# centerpoint.net
KiCad netlist of a schematic drawn in EAGLE
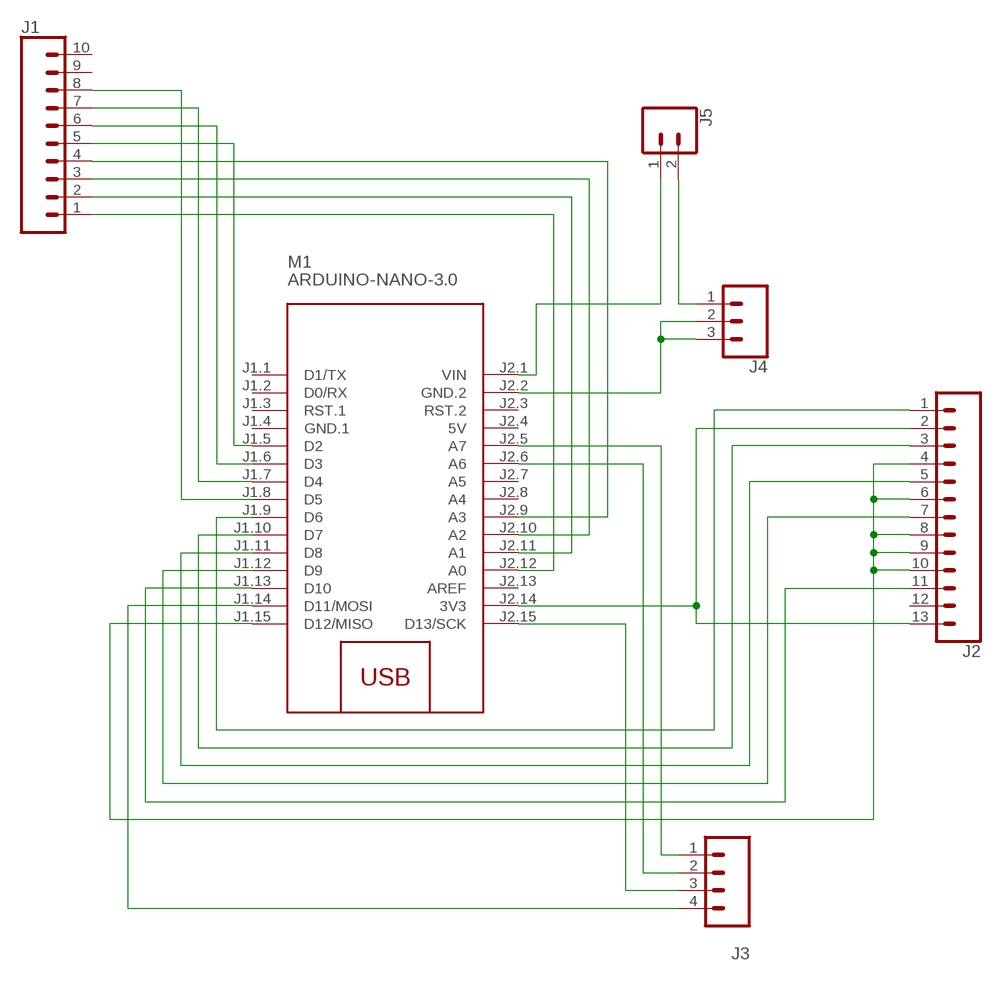
[diagram p0: schematic, sheet 1]

(export (version "E")
  (design (tool "Eeschema 10.0.6"))
  (components
    (comp (ref "J1")
      (value "CONN_10\"")
      (footprint "eagle-import:1X10")
      (libsource (lib "eagle-import") (part "CONN_10{dblquote}"))
    )
    (comp (ref "J2")
      (value "CONN_13")
      (footprint "eagle-import:1X13")
      (libsource (lib "eagle-import") (part "CONN_13"))
    )
    (comp (ref "J3")
      (value "CONN_04PTH")
      (footprint "eagle-import:1X04")
      (libsource (lib "eagle-import") (part "CONN_04PTH"))
    )
    (comp (ref "J4")
      (value "CONN_03-SCREW-5MM")
      (footprint "eagle-import:SCREWTERMINAL-5MM-3")
      (libsource (lib "eagle-import") (part "CONN_03-SCREW-5MM"))
    )
    (comp (ref "J5")
      (value "CONN_023.5MM")
      (footprint "eagle-import:SCREWTERMINAL-3.5MM-2")
      (libsource (lib "eagle-import") (part "CONN_023.5MM"))
    )
    (comp (ref "M1")
      (value "ARDUINO-NANO-3.0")
      (footprint "eagle-import:ARDUINO-NANO-3.0")
      (libsource (lib "eagle-import") (part "ARDUINO-NANO-3.0"))
    )
  )
  (nets
    (net (code "1") (name "/5V") (class "Default")
      (node (ref "M1") (pin "J2.4") (pinfunction "5V_J2.4") (pintype "power_in"))
    )
    (net (code "2") (name "/GND.1") (class "Default")
      (node (ref "M1") (pin "J1.4") (pinfunction "GND.1_J1.4") (pintype "power_in"))
    )
    (net (code "3") (name "Net-(J4-Pad1)") (class "Default")
      (node (ref "J4") (pin "1") (pinfunction "1_1") (pintype "passive"))
      (node (ref "J5") (pin "2") (pinfunction "2_2") (pintype "passive"))
    )
    (net (code "4") (name "Net-(M1-3V3)") (class "Default")
      (node (ref "J2") (pin "13") (pinfunction "13_13") (pintype "passive"))
      (node (ref "J2") (pin "2") (pinfunction "2_2") (pintype "passive"))
      (node (ref "M1") (pin "J2.14") (pinfunction "3V3_J2.14") (pintype "power_in"))
    )
    (net (code "5") (name "Net-(M1-A0)") (class "Default")
      (node (ref "J1") (pin "1") (pinfunction "1_1") (pintype "passive"))
      (node (ref "M1") (pin "J2.12") (pinfunction "A0_J2.12") (pintype "bidirectional"))
    )
    (net (code "6") (name "Net-(M1-A1)") (class "Default")
      (node (ref "J1") (pin "2") (pinfunction "2_2") (pintype "passive"))
      (node (ref "M1") (pin "J2.11") (pinfunction "A1_J2.11") (pintype "bidirectional"))
    )
    (net (code "7") (name "Net-(M1-A2)") (class "Default")
      (node (ref "J1") (pin "3") (pinfunction "3_3") (pintype "passive"))
      (node (ref "M1") (pin "J2.10") (pinfunction "A2_J2.10") (pintype "bidirectional"))
    )
    (net (code "8") (name "Net-(M1-A3)") (class "Default")
      (node (ref "J1") (pin "4") (pinfunction "4_4") (pintype "passive"))
      (node (ref "M1") (pin "J2.9") (pinfunction "A3_J2.9") (pintype "bidirectional"))
    )
    (net (code "9") (name "Net-(M1-A6)") (class "Default")
      (node (ref "J3") (pin "2") (pinfunction "2_2") (pintype "passive"))
      (node (ref "M1") (pin "J2.6") (pinfunction "A6_J2.6") (pintype "bidirectional"))
    )
    (net (code "10") (name "Net-(M1-A7)") (class "Default")
      (node (ref "J3") (pin "1") (pinfunction "1_1") (pintype "passive"))
      (node (ref "M1") (pin "J2.5") (pinfunction "A7_J2.5") (pintype "bidirectional"))
    )
    (net (code "11") (name "Net-(M1-D2)") (class "Default")
      (node (ref "J1") (pin "5") (pinfunction "5_5") (pintype "passive"))
      (node (ref "M1") (pin "J1.5") (pinfunction "D2_J1.5") (pintype "bidirectional"))
    )
    (net (code "12") (name "Net-(M1-D3)") (class "Default")
      (node (ref "J1") (pin "6") (pinfunction "6_6") (pintype "passive"))
      (node (ref "M1") (pin "J1.6") (pinfunction "D3_J1.6") (pintype "bidirectional"))
    )
    (net (code "13") (name "Net-(M1-D4)") (class "Default")
      (node (ref "J1") (pin "7") (pinfunction "7_7") (pintype "passive"))
      (node (ref "M1") (pin "J1.7") (pinfunction "D4_J1.7") (pintype "bidirectional"))
    )
    (net (code "14") (name "Net-(M1-D5)") (class "Default")
      (node (ref "J1") (pin "8") (pinfunction "8_8") (pintype "passive"))
      (node (ref "M1") (pin "J1.8") (pinfunction "D5_J1.8") (pintype "bidirectional"))
    )
    (net (code "15") (name "Net-(M1-D6)") (class "Default")
      (node (ref "J2") (pin "1") (pinfunction "1_1") (pintype "passive"))
      (node (ref "M1") (pin "J1.9") (pinfunction "D6_J1.9") (pintype "bidirectional"))
    )
    (net (code "16") (name "Net-(M1-D7)") (class "Default")
      (node (ref "J2") (pin "3") (pinfunction "3_3") (pintype "passive"))
      (node (ref "M1") (pin "J1.10") (pinfunction "D7_J1.10") (pintype "bidirectional"))
    )
    (net (code "17") (name "Net-(M1-D8)") (class "Default")
      (node (ref "J2") (pin "5") (pinfunction "5_5") (pintype "passive"))
      (node (ref "M1") (pin "J1.11") (pinfunction "D8_J1.11") (pintype "bidirectional"))
    )
    (net (code "18") (name "Net-(M1-D9)") (class "Default")
      (node (ref "J2") (pin "7") (pinfunction "7_7") (pintype "passive"))
      (node (ref "M1") (pin "J1.12") (pinfunction "D9_J1.12") (pintype "bidirectional"))
    )
    (net (code "19") (name "Net-(M1-D10)") (class "Default")
      (node (ref "J2") (pin "11") (pinfunction "11_11") (pintype "passive"))
      (node (ref "M1") (pin "J1.13") (pinfunction "D10_J1.13") (pintype "bidirectional"))
    )
    (net (code "20") (name "Net-(M1-D11{slash}MOSI)") (class "Default")
      (node (ref "J3") (pin "4") (pinfunction "4_4") (pintype "passive"))
      (node (ref "M1") (pin "J1.14") (pinfunction "D11/MOSI_J1.14") (pintype "bidirectional"))
    )
    (net (code "21") (name "Net-(M1-D12{slash}MISO)") (class "Default")
      (node (ref "J2") (pin "10") (pinfunction "10_10") (pintype "passive"))
      (node (ref "J2") (pin "4") (pinfunction "4_4") (pintype "passive"))
      (node (ref "J2") (pin "6") (pinfunction "6_6") (pintype "passive"))
      (node (ref "J2") (pin "8") (pinfunction "8_8") (pintype "passive"))
      (node (ref "J2") (pin "9") (pinfunction "9_9") (pintype "passive"))
      (node (ref "M1") (pin "J1.15") (pinfunction "D12/MISO_J1.15") (pintype "bidirectional"))
    )
    (net (code "22") (name "Net-(M1-D13{slash}SCK)") (class "Default")
      (node (ref "J3") (pin "3") (pinfunction "3_3") (pintype "passive"))
      (node (ref "M1") (pin "J2.15") (pinfunction "D13/SCK_J2.15") (pintype "bidirectional"))
    )
    (net (code "23") (name "Net-(M1-GND.2)") (class "Default")
      (node (ref "J4") (pin "2") (pinfunction "2_2") (pintype "passive"))
      (node (ref "J4") (pin "3") (pinfunction "3_3") (pintype "passive"))
      (node (ref "M1") (pin "J2.2") (pinfunction "GND.2_J2.2") (pintype "power_in"))
    )
    (net (code "24") (name "Net-(M1-VIN)") (class "Default")
      (node (ref "J5") (pin "1") (pinfunction "1_1") (pintype "passive"))
      (node (ref "M1") (pin "J2.1") (pinfunction "VIN_J2.1") (pintype "power_in"))
    )
    (net (code "25") (name "unconnected-(J1-Pad9)") (class "Default")
      (node (ref "J1") (pin "9") (pinfunction "9_9") (pintype "passive"))
    )
    (net (code "26") (name "unconnected-(J1-Pad10)") (class "Default")
      (node (ref "J1") (pin "10") (pinfunction "10_10") (pintype "passive"))
    )
    (net (code "27") (name "unconnected-(J2-Pad12)") (class "Default")
      (node (ref "J2") (pin "12") (pinfunction "12_12") (pintype "passive"))
    )
    (net (code "28") (name "unconnected-(M1-A4-PadJ2.8)") (class "Default")
      (node (ref "M1") (pin "J2.8") (pinfunction "A4_J2.8") (pintype "bidirectional"))
    )
    (net (code "29") (name "unconnected-(M1-A5-PadJ2.7)") (class "Default")
      (node (ref "M1") (pin "J2.7") (pinfunction "A5_J2.7") (pintype "bidirectional"))
    )
    (net (code "30") (name "unconnected-(M1-AREF-PadJ2.13)") (class "Default")
      (node (ref "M1") (pin "J2.13") (pinfunction "AREF_J2.13") (pintype "bidirectional"))
    )
    (net (code "31") (name "unconnected-(M1-D0{slash}RX-PadJ1.2)") (class "Default")
      (node (ref "M1") (pin "J1.2") (pinfunction "D0/RX_J1.2") (pintype "bidirectional"))
    )
    (net (code "32") (name "unconnected-(M1-D1{slash}TX-PadJ1.1)") (class "Default")
      (node (ref "M1") (pin "J1.1") (pinfunction "D1/TX_J1.1") (pintype "bidirectional"))
    )
    (net (code "33") (name "unconnected-(M1-RST.1-PadJ1.3)") (class "Default")
      (node (ref "M1") (pin "J1.3") (pinfunction "RST.1_J1.3") (pintype "bidirectional"))
    )
    (net (code "34") (name "unconnected-(M1-RST.2-PadJ2.3)") (class "Default")
      (node (ref "M1") (pin "J2.3") (pinfunction "RST.2_J2.3") (pintype "bidirectional"))
    )
  )
)
